# node_board_rony.net
KiCad netlist of a schematic drawn in EAGLE
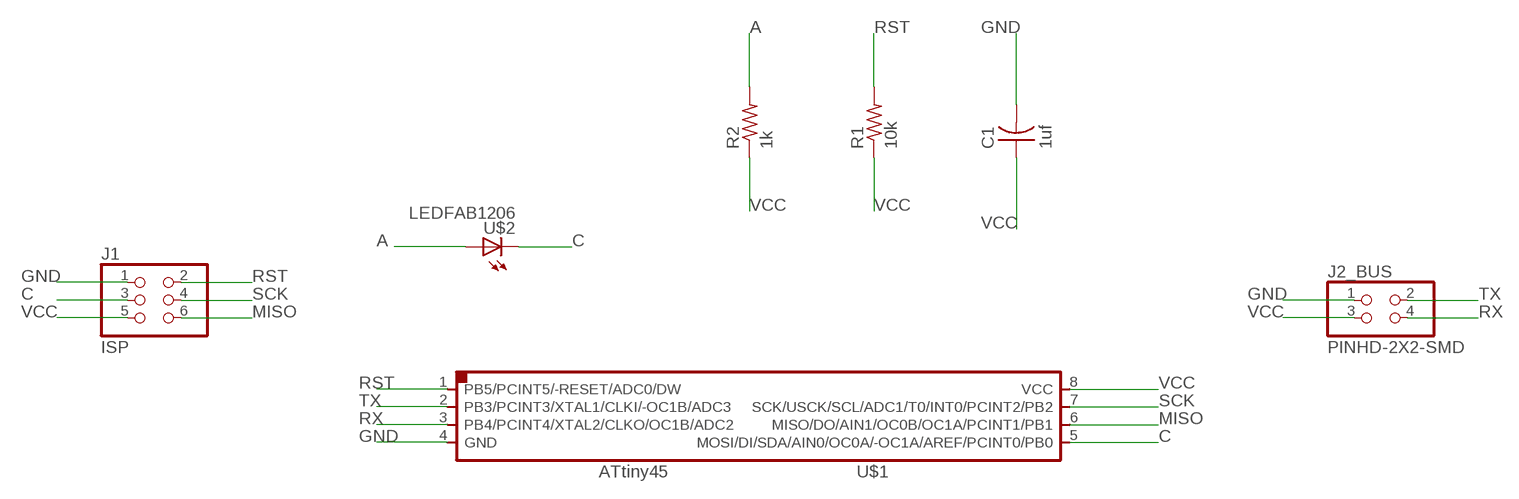
[diagram p0: schematic, sheet 1]

(export (version "E")
  (design (tool "Eeschema 10.0.6"))
  (components
    (comp (ref "C1")
      (value "1uf")
      (footprint "eagle-import:C1206FAB")
      (libsource (lib "eagle-import") (part "CAP-US1206FAB"))
    )
    (comp (ref "J1")
      (value "ISP")
      (footprint "eagle-import:2X03SMD")
      (libsource (lib "eagle-import") (part "PINHD-2X3-SMD"))
    )
    (comp (ref "J2_BUS")
      (value "PINHD-2X2-SMD")
      (footprint "eagle-import:2X02SMD")
      (libsource (lib "eagle-import") (part "PINHD-2X2-SMD"))
    )
    (comp (ref "R1")
      (value "10k")
      (footprint "eagle-import:R1206FAB")
      (libsource (lib "eagle-import") (part "RES-US1206FAB"))
    )
    (comp (ref "R2")
      (value "1k")
      (footprint "eagle-import:R1206FAB")
      (libsource (lib "eagle-import") (part "RES-US1206FAB"))
    )
    (comp (ref "U$1")
      (value "ATTINY45SI")
      (footprint "eagle-import:SOIC8")
      (libsource (lib "eagle-import") (part "ATTINY45SI"))
    )
    (comp (ref "U$2")
      (value "LEDFAB1206")
      (footprint "eagle-import:LED1206FAB")
      (libsource (lib "eagle-import") (part "LEDFAB1206"))
    )
  )
  (nets
    (net (code "1") (name "/A") (class "Default")
      (node (ref "R2") (pin "2") (pinfunction "2_2") (pintype "passive"))
      (node (ref "U$2") (pin "1") (pinfunction "A_1") (pintype "passive"))
    )
    (net (code "2") (name "/C") (class "Default")
      (node (ref "J1") (pin "3") (pinfunction "3_3") (pintype "passive"))
      (node (ref "U$1") (pin "5") (pinfunction "MOSI/DI/SDA/AIN0/OC0A/-OC1A/AREF/PCINT0/PB0_5") (pintype "bidirectional"))
      (node (ref "U$2") (pin "2") (pinfunction "C_2") (pintype "passive"))
    )
    (net (code "3") (name "/GND") (class "Default")
      (node (ref "C1") (pin "2") (pinfunction "2_2") (pintype "passive"))
      (node (ref "J1") (pin "1") (pinfunction "1_1") (pintype "passive"))
      (node (ref "J2_BUS") (pin "1") (pinfunction "1_1") (pintype "passive"))
      (node (ref "U$1") (pin "4") (pinfunction "GND_4") (pintype "bidirectional"))
    )
    (net (code "4") (name "/MISO") (class "Default")
      (node (ref "J1") (pin "6") (pinfunction "6_6") (pintype "passive"))
      (node (ref "U$1") (pin "6") (pinfunction "MISO/DO/AIN1/OC0B/OC1A/PCINT1/PB1_6") (pintype "bidirectional"))
    )
    (net (code "5") (name "/RST") (class "Default")
      (node (ref "J1") (pin "2") (pinfunction "2_2") (pintype "passive"))
      (node (ref "R1") (pin "2") (pinfunction "2_2") (pintype "passive"))
      (node (ref "U$1") (pin "1") (pinfunction "PB5/PCINT5/-RESET/ADC0/DW_1") (pintype "bidirectional"))
    )
    (net (code "6") (name "/RX") (class "Default")
      (node (ref "J2_BUS") (pin "4") (pinfunction "4_4") (pintype "passive"))
      (node (ref "U$1") (pin "3") (pinfunction "PB4/PCINT4/XTAL2/CLKO/OC1B/ADC2_3") (pintype "bidirectional"))
    )
    (net (code "7") (name "/SCK") (class "Default")
      (node (ref "J1") (pin "4") (pinfunction "4_4") (pintype "passive"))
      (node (ref "U$1") (pin "7") (pinfunction "SCK/USCK/SCL/ADC1/T0/INT0/PCINT2/PB2_7") (pintype "bidirectional"))
    )
    (net (code "8") (name "/TX") (class "Default")
      (node (ref "J2_BUS") (pin "2") (pinfunction "2_2") (pintype "passive"))
      (node (ref "U$1") (pin "2") (pinfunction "PB3/PCINT3/XTAL1/CLKI/-OC1B/ADC3_2") (pintype "bidirectional"))
    )
    (net (code "9") (name "/VCC") (class "Default")
      (node (ref "C1") (pin "1") (pinfunction "1_1") (pintype "passive"))
      (node (ref "J1") (pin "5") (pinfunction "5_5") (pintype "passive"))
      (node (ref "J2_BUS") (pin "3") (pinfunction "3_3") (pintype "passive"))
      (node (ref "R1") (pin "1") (pinfunction "1_1") (pintype "passive"))
      (node (ref "R2") (pin "1") (pinfunction "1_1") (pintype "passive"))
      (node (ref "U$1") (pin "8") (pinfunction "VCC_8") (pintype "bidirectional"))
    )
  )
)
